# mainSchem.net
KiCad netlist of a schematic drawn in Altium Designer
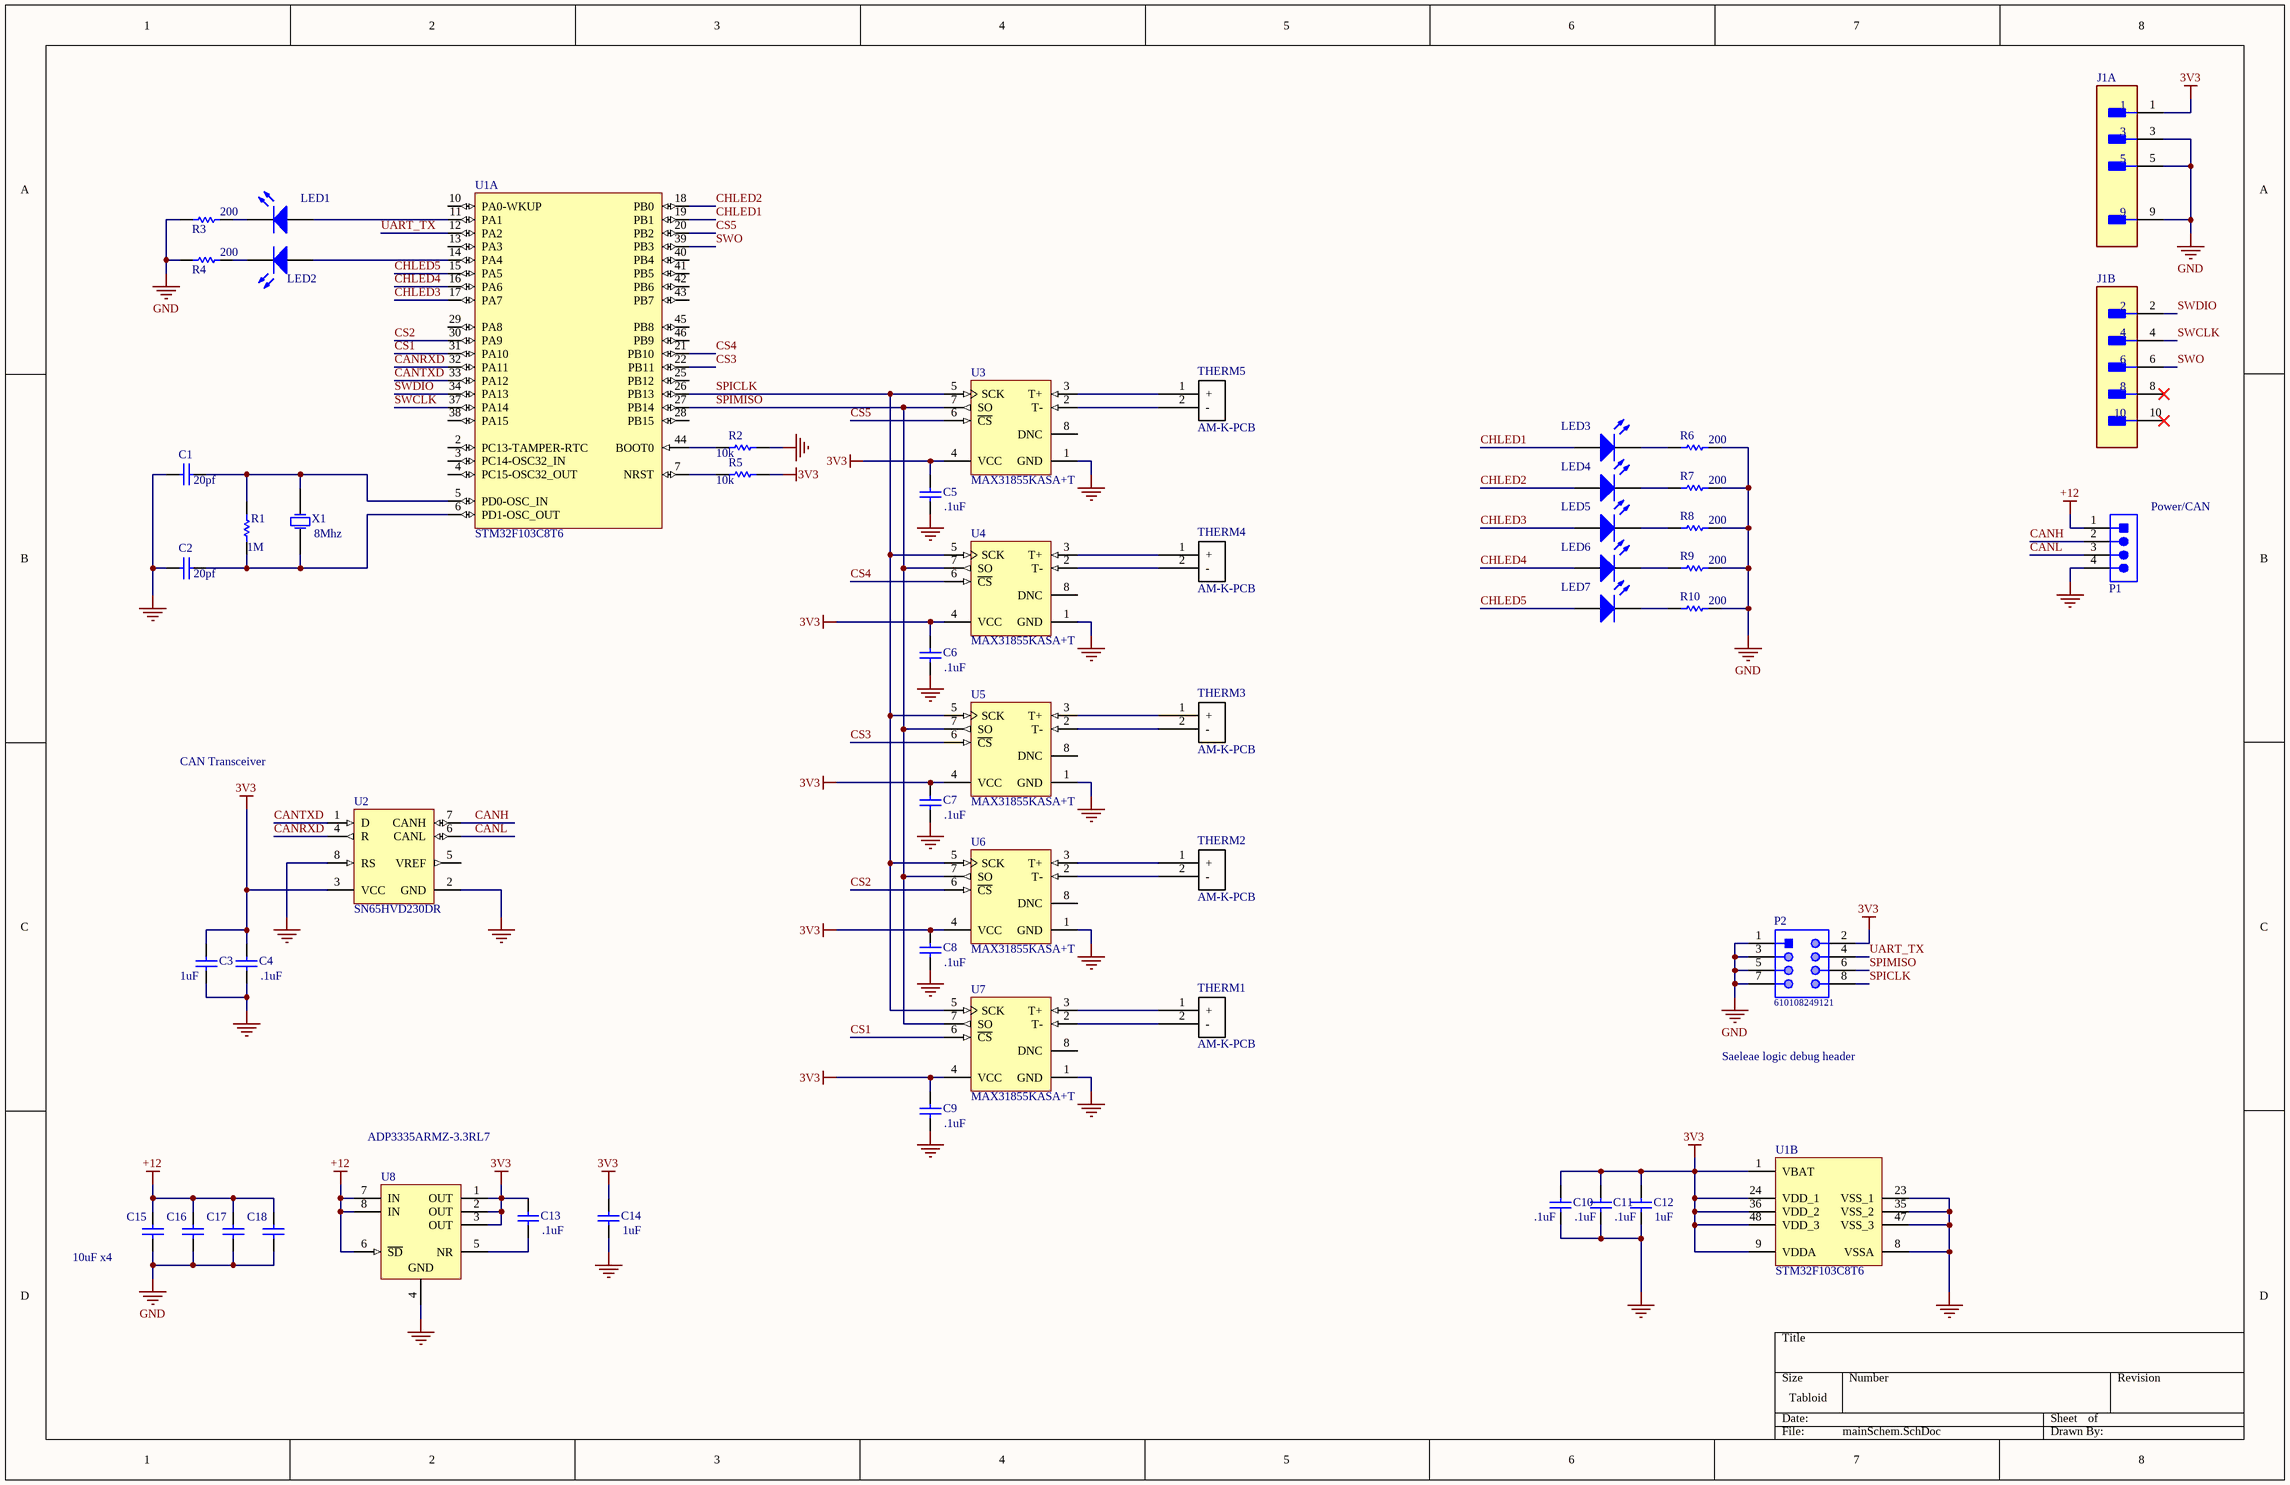
[diagram p0: mainSchem.SchDoc]

(export (version "E")
  (design (tool "Eeschema 10.0.6"))
  (components
    (comp (ref "C1")
      (value "08051A200JAT2A")
      (footprint "CAPC2013X140X50NL20T25")
      (fields (field (name "MANUFACTURER") "AVX Interconnect / Elco"))
      (libsource (lib "Altium Content Vault") (part "CAP"))
    )
    (comp (ref "C2")
      (value "08051A200JAT2A")
      (footprint "CAPC2013X140X50NL20T25")
      (fields (field (name "MANUFACTURER") "AVX Interconnect / Elco"))
      (libsource (lib "Altium Content Vault") (part "CAP"))
    )
    (comp (ref "C3")
      (value "GRM31MR71H105KA88L")
      (footprint "CAPC3216X125X55LL15T25")
      (description "Chip Capacitor, 1 uF, +/- 10%, 50 V, -55 to 125 degC, 1206 (3216 Metric), RoHS, Tape and Reel")
      (fields (field (name "TOLERANCE") "10%") (field (name "MANUFACTURER") "Murata"))
      (libsource (lib "Altium Content Vault") (part "CAP-NP-2"))
    )
    (comp (ref "C4")
      (value "12065C104KAT2A")
      (footprint "CAPC3216X94X50ML20T25")
      (description "Chip Capacitor, Ceramic, 100 nF, 10%, 50 V, 1206, RoHS, Tape and Reel")
      (fields (field (name "MANUFACTURER") "AVX"))
      (libsource (lib "Altium Content Vault") (part "CAP-NP-2"))
    )
    (comp (ref "C5")
      (value "CGA3E2X7R1H104K080AA")
      (footprint "CAPC1608X90X20LL10")
      (description "Chip Capacitor, 0.1 uF, +/- 10%, 50 V, -55 to 125 degC, 0603 (1608 Metric), RoHS, Tape and Reel")
      (fields (field (name "VOLTAGE") "50V") (field (name "TOLERANCE") "10%"))
      (libsource (lib "Altium Content Vault") (part "CAP-NP-2"))
    )
    (comp (ref "C6")
      (value "CGA3E2X7R1H104K080AA")
      (footprint "CAPC1608X90X20LL10")
      (description "Chip Capacitor, 0.1 uF, +/- 10%, 50 V, -55 to 125 degC, 0603 (1608 Metric), RoHS, Tape and Reel")
      (fields (field (name "VOLTAGE") "50V") (field (name "TOLERANCE") "10%"))
      (libsource (lib "Altium Content Vault") (part "CAP-NP-2"))
    )
    (comp (ref "C7")
      (value "CGA3E2X7R1H104K080AA")
      (footprint "CAPC1608X90X20LL10")
      (description "Chip Capacitor, 0.1 uF, +/- 10%, 50 V, -55 to 125 degC, 0603 (1608 Metric), RoHS, Tape and Reel")
      (fields (field (name "VOLTAGE") "50V") (field (name "TOLERANCE") "10%"))
      (libsource (lib "Altium Content Vault") (part "CAP-NP-2"))
    )
    (comp (ref "C8")
      (value "CGA3E2X7R1H104K080AA")
      (footprint "CAPC1608X90X20LL10")
      (description "Chip Capacitor, 0.1 uF, +/- 10%, 50 V, -55 to 125 degC, 0603 (1608 Metric), RoHS, Tape and Reel")
      (fields (field (name "VOLTAGE") "50V") (field (name "TOLERANCE") "10%"))
      (libsource (lib "Altium Content Vault") (part "CAP-NP-2"))
    )
    (comp (ref "C9")
      (value "CGA3E2X7R1H104K080AA")
      (footprint "CAPC1608X90X20LL10")
      (description "Chip Capacitor, 0.1 uF, +/- 10%, 50 V, -55 to 125 degC, 0603 (1608 Metric), RoHS, Tape and Reel")
      (fields (field (name "VOLTAGE") "50V") (field (name "TOLERANCE") "10%"))
      (libsource (lib "Altium Content Vault") (part "CAP-NP-2"))
    )
    (comp (ref "C10")
      (value "12065C104KAT2A")
      (footprint "CAPC3216X94X50ML20T25")
      (description "Chip Capacitor, Ceramic, 100 nF, 10%, 50 V, 1206, RoHS, Tape and Reel")
      (fields (field (name "MANUFACTURER") "AVX"))
      (libsource (lib "Altium Content Vault") (part "CAP-NP-2"))
    )
    (comp (ref "C11")
      (value "12065C104KAT2A")
      (footprint "CAPC3216X94X50ML20T25")
      (description "Chip Capacitor, Ceramic, 100 nF, 10%, 50 V, 1206, RoHS, Tape and Reel")
      (fields (field (name "MANUFACTURER") "AVX"))
      (libsource (lib "Altium Content Vault") (part "CAP-NP-2"))
    )
    (comp (ref "C12")
      (value "12065C104KAT2A")
      (footprint "CAPC3216X94X50ML20T25")
      (description "Chip Capacitor, Ceramic, 100 nF, 10%, 50 V, 1206, RoHS, Tape and Reel")
      (fields (field (name "MANUFACTURER") "AVX"))
      (libsource (lib "Altium Content Vault") (part "CAP-NP-2"))
    )
    (comp (ref "C13")
      (value "CGA3E2X7R1H104K080AA")
      (footprint "CAPC1608X90X20LL10")
      (description "Chip Capacitor, 0.1 uF, +/- 10%, 50 V, -55 to 125 degC, 0603 (1608 Metric), RoHS, Tape and Reel")
      (fields (field (name "VOLTAGE") "50V") (field (name "TOLERANCE") "10%"))
      (libsource (lib "Altium Content Vault") (part "CAP-NP-2"))
    )
    (comp (ref "C14")
      (value "GRM31MR71H105KA88L")
      (footprint "CAPC3216X125X55LL15T25")
      (description "Chip Capacitor, 1 uF, +/- 10%, 50 V, -55 to 125 degC, 1206 (3216 Metric), RoHS, Tape and Reel")
      (fields (field (name "TOLERANCE") "10%") (field (name "MANUFACTURER") "Murata"))
      (libsource (lib "Altium Content Vault") (part "CAP-NP-2"))
    )
    (comp (ref "C15")
      (value "CGA5L3X5R1H106K160AB")
      (footprint "CAPC3216X190X20LL20")
      (description "Chip Capacitor, 10 uF, +/- 10%, 50 V, -55 to 85 degC, 1206 (3216 Metric), RoHS, Tape and Reel")
      (fields (field (name "MANUFACTURER") "TDK") (field (name "TOLERANCE") "10%"))
      (libsource (lib "Altium Content Vault") (part "CAP-NP-2"))
    )
    (comp (ref "C16")
      (value "CGA5L3X5R1H106K160AB")
      (footprint "CAPC3216X190X20LL20")
      (description "Chip Capacitor, 10 uF, +/- 10%, 50 V, -55 to 85 degC, 1206 (3216 Metric), RoHS, Tape and Reel")
      (fields (field (name "MANUFACTURER") "TDK") (field (name "TOLERANCE") "10%"))
      (libsource (lib "Altium Content Vault") (part "CAP-NP-2"))
    )
    (comp (ref "C17")
      (value "CGA5L3X5R1H106K160AB")
      (footprint "CAPC3216X190X20LL20")
      (description "Chip Capacitor, 10 uF, +/- 10%, 50 V, -55 to 85 degC, 1206 (3216 Metric), RoHS, Tape and Reel")
      (fields (field (name "MANUFACTURER") "TDK") (field (name "TOLERANCE") "10%"))
      (libsource (lib "Altium Content Vault") (part "CAP-NP-2"))
    )
    (comp (ref "C18")
      (value "CGA5L3X5R1H106K160AB")
      (footprint "CAPC3216X190X20LL20")
      (description "Chip Capacitor, 10 uF, +/- 10%, 50 V, -55 to 85 degC, 1206 (3216 Metric), RoHS, Tape and Reel")
      (fields (field (name "MANUFACTURER") "TDK") (field (name "TOLERANCE") "10%"))
      (libsource (lib "Altium Content Vault") (part "CAP-NP-2"))
    )
    (comp (ref "J1")
      (value "FTSH-105-01-L-DV-007-K")
      (footprint "FP-FTSH-105-01-L-DV-007-K-MFG")
      (description "CONN HEADER SMD 10POS 1.27MM")
      (fields
        (field (name "OCTOPART") "https://octopart.com/ftsh-105-01-l-dv-007-k-samtec-53647300")
        (field (name "MANUFACTURER") "Samtec")
      )
      (libsource (lib "Altium Content Vault") (part "7c368be3265735b2816d0cab4417f87"))
    )
    (comp (ref "LED1")
      (value "150120GS75000")
      (footprint "1206_A")
      (description "SMD mono-color Chip LED, WL-SMCW, Green")
      (fields (field (name "MANUFACTURER") "Wuerth Elektronik"))
      (libsource (lib "Altium Content Vault") (part "WE-LED_K1A2-2"))
    )
    (comp (ref "LED2")
      (value "150120GS75000")
      (footprint "1206_A")
      (description "SMD mono-color Chip LED, WL-SMCW, Green")
      (fields (field (name "MANUFACTURER") "Wuerth Elektronik"))
      (libsource (lib "Altium Content Vault") (part "WE-LED_K1A2-2"))
    )
    (comp (ref "LED3")
      (value "150120GS75000")
      (footprint "1206_A")
      (description "SMD mono-color Chip LED, WL-SMCW, Green")
      (fields (field (name "MANUFACTURER") "Wuerth Elektronik"))
      (libsource (lib "Altium Content Vault") (part "WE-LED_K1A2-2"))
    )
    (comp (ref "LED4")
      (value "150120GS75000")
      (footprint "1206_A")
      (description "SMD mono-color Chip LED, WL-SMCW, Green")
      (fields (field (name "MANUFACTURER") "Wuerth Elektronik"))
      (libsource (lib "Altium Content Vault") (part "WE-LED_K1A2-2"))
    )
    (comp (ref "LED5")
      (value "150120GS75000")
      (footprint "1206_A")
      (description "SMD mono-color Chip LED, WL-SMCW, Green")
      (fields (field (name "MANUFACTURER") "Wuerth Elektronik"))
      (libsource (lib "Altium Content Vault") (part "WE-LED_K1A2-2"))
    )
    (comp (ref "LED6")
      (value "150120GS75000")
      (footprint "1206_A")
      (description "SMD mono-color Chip LED, WL-SMCW, Green")
      (fields (field (name "MANUFACTURER") "Wuerth Elektronik"))
      (libsource (lib "Altium Content Vault") (part "WE-LED_K1A2-2"))
    )
    (comp (ref "LED7")
      (value "150120GS75000")
      (footprint "1206_A")
      (description "SMD mono-color Chip LED, WL-SMCW, Green")
      (fields (field (name "MANUFACTURER") "Wuerth Elektronik"))
      (libsource (lib "Altium Content Vault") (part "WE-LED_K1A2-2"))
    )
    (comp (ref "P1")
      (value "B4B-PH-K-S(LF)(SN)")
      (footprint "JST-B4B-PH-K-S_V")
      (fields (field (name "MANUFACTURER") "JST"))
      (libsource (lib "Altium Content Vault") (part "CN-1P-M-R4"))
    )
    (comp (ref "P2")
      (value "610108249121")
      (footprint "610108249121")
      (description "SMT Angled Pin Header WR-PHD, Pitch 2.54 mm, Dual Row, 8 pins")
      (fields (field (name "MANUFACTURER") "Wurth Elektronik") (field (name "PUBLISHER") "WurthElektronik"))
      (libsource (lib "Altium Content Vault") (part "WE-CN-2P-M-R8"))
    )
    (comp (ref "R1")
      (value "ERJ-8ENF1004V")
      (footprint "RESC3216X70X50NL05T20")
      (fields (field (name "MANUFACTURER") "Panasonic"))
      (libsource (lib "Altium Content Vault") (part "RES"))
    )
    (comp (ref "R2")
      (value "ERJ3EKF1002V")
      (footprint "RESC1609X55X30LL15T15")
      (description "Chip Resistor, 10 KOhm, +/- 1%, 0.1 W, -55 to 155 degC, 0603 (1608 Metric), RoHS, Tape and Reel")
      (fields (field (name "TOLERANCE") "1%") (field (name "MANUFACTURER") "Panasonic"))
      (libsource (lib "Altium Content Vault") (part "RES-2"))
    )
    (comp (ref "R3")
      (value "CRCW1206200RFKEA")
      (footprint "RESC3216X60X45ML10T20")
      (fields (field (name "MANUFACTURER") "Vishay Dale"))
      (libsource (lib "Altium Content Vault") (part "RES"))
    )
    (comp (ref "R4")
      (value "CRCW1206200RFKEA")
      (footprint "RESC3216X60X45ML10T20")
      (fields (field (name "MANUFACTURER") "Vishay Dale"))
      (libsource (lib "Altium Content Vault") (part "RES"))
    )
    (comp (ref "R5")
      (value "ERJ3EKF1002V")
      (footprint "RESC1609X55X30LL15T15")
      (description "Chip Resistor, 10 KOhm, +/- 1%, 0.1 W, -55 to 155 degC, 0603 (1608 Metric), RoHS, Tape and Reel")
      (fields (field (name "TOLERANCE") "1%") (field (name "MANUFACTURER") "Panasonic"))
      (libsource (lib "Altium Content Vault") (part "RES-2"))
    )
    (comp (ref "R6")
      (value "CRCW0603200RFKEA")
      (footprint "RESC1609X50X30NL10T20")
      (fields (field (name "MANUFACTURER") "Vishay Dale"))
      (libsource (lib "Altium Content Vault") (part "RES"))
    )
    (comp (ref "R7")
      (value "CRCW0603200RFKEA")
      (footprint "RESC1609X50X30NL10T20")
      (fields (field (name "MANUFACTURER") "Vishay Dale"))
      (libsource (lib "Altium Content Vault") (part "RES"))
    )
    (comp (ref "R8")
      (value "CRCW0603200RFKEA")
      (footprint "RESC1609X50X30NL10T20")
      (fields (field (name "MANUFACTURER") "Vishay Dale"))
      (libsource (lib "Altium Content Vault") (part "RES"))
    )
    (comp (ref "R9")
      (value "CRCW0603200RFKEA")
      (footprint "RESC1609X50X30NL10T20")
      (fields (field (name "MANUFACTURER") "Vishay Dale"))
      (libsource (lib "Altium Content Vault") (part "RES"))
    )
    (comp (ref "R10")
      (value "CRCW0603200RFKEA")
      (footprint "RESC1609X50X30NL10T20")
      (fields (field (name "MANUFACTURER") "Vishay Dale"))
      (libsource (lib "Altium Content Vault") (part "RES"))
    )
    (comp (ref "THERM1")
      (value "AM-K-PCB")
      (footprint "Type K Connector")
      (libsource (lib "Type K Connector Lib") (part "Type K Thermocoulple Conn."))
    )
    (comp (ref "THERM2")
      (value "AM-K-PCB")
      (footprint "Type K Connector")
      (libsource (lib "Type K Connector Lib") (part "Type K Thermocoulple Conn."))
    )
    (comp (ref "THERM3")
      (value "AM-K-PCB")
      (footprint "Type K Connector")
      (libsource (lib "Type K Connector Lib") (part "Type K Thermocoulple Conn."))
    )
    (comp (ref "THERM4")
      (value "AM-K-PCB")
      (footprint "Type K Connector")
      (libsource (lib "Type K Connector Lib") (part "Type K Thermocoulple Conn."))
    )
    (comp (ref "THERM5")
      (value "AM-K-PCB")
      (footprint "Type K Connector")
      (libsource (lib "Type K Connector Lib") (part "Type K Thermocoulple Conn."))
    )
    (comp (ref "U1")
      (value "STM32F103C8T6")
      (footprint "STM-LQFP48_L")
      (libsource (lib "Altium Content Vault") (part "MC-ARM-STM32F103X8_B-SQ48"))
    )
    (comp (ref "U2")
      (value "SN65HVD230DR")
      (footprint "D0008A_L")
      (fields (field (name "MANUFACTURER") "Texas Instruments"))
      (libsource (lib "Altium Content Vault") (part "TI-SN65HVD230-SOIC_D-8"))
    )
    (comp (ref "U3")
      (value "MAX31855KASA+T")
      (footprint "MAXM-S8+4_N")
      (fields (field (name "GENERIC PART NUMBER") "MAX31855"))
      (libsource (lib "Altium Content Vault") (part "MAX31855-S8+4"))
    )
    (comp (ref "U4")
      (value "MAX31855KASA+T")
      (footprint "MAXM-S8+4_N")
      (fields (field (name "GENERIC PART NUMBER") "MAX31855"))
      (libsource (lib "Altium Content Vault") (part "MAX31855-S8+4"))
    )
    (comp (ref "U5")
      (value "MAX31855KASA+T")
      (footprint "MAXM-S8+4_N")
      (fields (field (name "GENERIC PART NUMBER") "MAX31855"))
      (libsource (lib "Altium Content Vault") (part "MAX31855-S8+4"))
    )
    (comp (ref "U6")
      (value "MAX31855KASA+T")
      (footprint "MAXM-S8+4_N")
      (fields (field (name "GENERIC PART NUMBER") "MAX31855"))
      (libsource (lib "Altium Content Vault") (part "MAX31855-S8+4"))
    )
    (comp (ref "U7")
      (value "MAX31855KASA+T")
      (footprint "MAXM-S8+4_N")
      (fields (field (name "GENERIC PART NUMBER") "MAX31855"))
      (libsource (lib "Altium Content Vault") (part "MAX31855-S8+4"))
    )
    (comp (ref "U8")
      (value "ADP3335ARMZ-3.3RL7")
      (footprint "ADI-RM-8_L")
      (fields (field (name "MANUFACTURER") "Analog Devices"))
      (libsource (lib "Altium Content Vault") (part "ADI-ADP3335-RM-8"))
    )
    (comp (ref "X1")
      (value "ABM3-8.000MHZ-D2Y-T")
      (footprint "ABRA-ABM3-2_V")
      (description "Miniature Ceramic Crystal, 8 MHz, -40 to 85 degC, 2-Pin SMD, RoHS, Tape and Reel")
      (fields (field (name "MANUFACTURER") "ABRACON") (field (name "TOLERANCE") "20PPM"))
      (libsource (lib "Altium Content Vault") (part "XTAL_1-2-2"))
    )
  )
  (nets
    (net (code "1") (name "+12") (class "Default")
      (node (ref "C15") (pin "1") (pinfunction "1_1") (pintype "passive"))
      (node (ref "C16") (pin "1") (pinfunction "1_1") (pintype "passive"))
      (node (ref "C17") (pin "1") (pinfunction "1_1") (pintype "passive"))
      (node (ref "C18") (pin "1") (pinfunction "1_1") (pintype "passive"))
      (node (ref "P1") (pin "1") (pinfunction "1_1") (pintype "passive"))
      (node (ref "U8") (pin "6") (pinfunction "~{SD}_6") (pintype "input"))
      (node (ref "U8") (pin "7") (pinfunction "IN_7") (pintype "power_in"))
      (node (ref "U8") (pin "8") (pinfunction "IN_8") (pintype "power_in"))
    )
    (net (code "2") (name "/CANH") (class "Default")
      (node (ref "P1") (pin "2") (pinfunction "2_2") (pintype "passive"))
      (node (ref "U2") (pin "7") (pinfunction "CANH_7") (pintype "bidirectional"))
    )
    (net (code "3") (name "/CANL") (class "Default")
      (node (ref "P1") (pin "3") (pinfunction "3_3") (pintype "passive"))
      (node (ref "U2") (pin "6") (pinfunction "CANL_6") (pintype "bidirectional"))
    )
    (net (code "4") (name "/CANRXD") (class "Default")
      (node (ref "U1") (pin "32") (pinfunction "PA11_32") (pintype "bidirectional"))
      (node (ref "U2") (pin "4") (pinfunction "R_4") (pintype "output"))
    )
    (net (code "5") (name "/CANTXD") (class "Default")
      (node (ref "U1") (pin "33") (pinfunction "PA12_33") (pintype "bidirectional"))
      (node (ref "U2") (pin "1") (pinfunction "D_1") (pintype "input"))
    )
    (net (code "6") (name "/CHLED1") (class "Default")
      (node (ref "LED3") (pin "2") (pinfunction "A_2") (pintype "passive"))
      (node (ref "U1") (pin "19") (pinfunction "PB1_19") (pintype "bidirectional"))
    )
    (net (code "7") (name "/CHLED2") (class "Default")
      (node (ref "LED4") (pin "2") (pinfunction "A_2") (pintype "passive"))
      (node (ref "U1") (pin "18") (pinfunction "PB0_18") (pintype "bidirectional"))
    )
    (net (code "8") (name "/CHLED3") (class "Default")
      (node (ref "LED5") (pin "2") (pinfunction "A_2") (pintype "passive"))
      (node (ref "U1") (pin "17") (pinfunction "PA7_17") (pintype "bidirectional"))
    )
    (net (code "9") (name "/CHLED4") (class "Default")
      (node (ref "LED6") (pin "2") (pinfunction "A_2") (pintype "passive"))
      (node (ref "U1") (pin "16") (pinfunction "PA6_16") (pintype "bidirectional"))
    )
    (net (code "10") (name "/CHLED5") (class "Default")
      (node (ref "LED7") (pin "2") (pinfunction "A_2") (pintype "passive"))
      (node (ref "U1") (pin "15") (pinfunction "PA5_15") (pintype "bidirectional"))
    )
    (net (code "11") (name "/CS1") (class "Default")
      (node (ref "U1") (pin "31") (pinfunction "PA10_31") (pintype "bidirectional"))
      (node (ref "U7") (pin "6") (pinfunction "~{CS}_6") (pintype "input"))
    )
    (net (code "12") (name "/CS2") (class "Default")
      (node (ref "U1") (pin "30") (pinfunction "PA9_30") (pintype "bidirectional"))
      (node (ref "U6") (pin "6") (pinfunction "~{CS}_6") (pintype "input"))
    )
    (net (code "13") (name "/CS3") (class "Default")
      (node (ref "U1") (pin "22") (pinfunction "PB11_22") (pintype "bidirectional"))
      (node (ref "U5") (pin "6") (pinfunction "~{CS}_6") (pintype "input"))
    )
    (net (code "14") (name "/CS4") (class "Default")
      (node (ref "U1") (pin "21") (pinfunction "PB10_21") (pintype "bidirectional"))
      (node (ref "U4") (pin "6") (pinfunction "~{CS}_6") (pintype "input"))
    )
    (net (code "15") (name "/CS5") (class "Default")
      (node (ref "U1") (pin "20") (pinfunction "PB2_20") (pintype "bidirectional"))
      (node (ref "U3") (pin "6") (pinfunction "~{CS}_6") (pintype "input"))
    )
    (net (code "16") (name "/SPICLK") (class "Default")
      (node (ref "P2") (pin "8") (pinfunction "8_8") (pintype "passive"))
      (node (ref "U1") (pin "26") (pinfunction "PB13_26") (pintype "bidirectional"))
      (node (ref "U3") (pin "5") (pinfunction "SCK_5") (pintype "input"))
      (node (ref "U4") (pin "5") (pinfunction "SCK_5") (pintype "input"))
      (node (ref "U5") (pin "5") (pinfunction "SCK_5") (pintype "input"))
      (node (ref "U6") (pin "5") (pinfunction "SCK_5") (pintype "input"))
      (node (ref "U7") (pin "5") (pinfunction "SCK_5") (pintype "input"))
    )
    (net (code "17") (name "/SPIMISO") (class "Default")
      (node (ref "P2") (pin "6") (pinfunction "6_6") (pintype "passive"))
      (node (ref "U1") (pin "27") (pinfunction "PB14_27") (pintype "bidirectional"))
      (node (ref "U3") (pin "7") (pinfunction "SO_7") (pintype "output"))
      (node (ref "U4") (pin "7") (pinfunction "SO_7") (pintype "output"))
      (node (ref "U5") (pin "7") (pinfunction "SO_7") (pintype "output"))
      (node (ref "U6") (pin "7") (pinfunction "SO_7") (pintype "output"))
      (node (ref "U7") (pin "7") (pinfunction "SO_7") (pintype "output"))
    )
    (net (code "18") (name "/SWCLK") (class "Default")
      (node (ref "J1") (pin "4") (pinfunction "4_4") (pintype "passive"))
      (node (ref "U1") (pin "37") (pinfunction "PA14_37") (pintype "bidirectional"))
    )
    (net (code "19") (name "/SWDIO") (class "Default")
      (node (ref "J1") (pin "2") (pinfunction "2_2") (pintype "passive"))
      (node (ref "U1") (pin "34") (pinfunction "PA13_34") (pintype "bidirectional"))
    )
    (net (code "20") (name "/SWO") (class "Default")
      (node (ref "J1") (pin "6") (pinfunction "6_6") (pintype "passive"))
      (node (ref "U1") (pin "39") (pinfunction "PB3_39") (pintype "bidirectional"))
    )
    (net (code "21") (name "/UART_TX") (class "Default")
      (node (ref "P2") (pin "4") (pinfunction "4_4") (pintype "passive"))
      (node (ref "U1") (pin "12") (pinfunction "PA2_12") (pintype "bidirectional"))
    )
    (net (code "22") (name "3V3") (class "Default")
      (node (ref "C10") (pin "1") (pinfunction "1_1") (pintype "passive"))
      (node (ref "C11") (pin "1") (pinfunction "1_1") (pintype "passive"))
      (node (ref "C12") (pin "1") (pinfunction "1_1") (pintype "passive"))
      (node (ref "C13") (pin "1") (pinfunction "1_1") (pintype "passive"))
      (node (ref "C14") (pin "1") (pinfunction "1_1") (pintype "passive"))
      (node (ref "C3") (pin "1") (pinfunction "1_1") (pintype "passive"))
      (node (ref "C4") (pin "1") (pinfunction "1_1") (pintype "passive"))
      (node (ref "C5") (pin "1") (pinfunction "1_1") (pintype "passive"))
      (node (ref "C6") (pin "1") (pinfunction "1_1") (pintype "passive"))
      (node (ref "C7") (pin "1") (pinfunction "1_1") (pintype "passive"))
      (node (ref "C8") (pin "1") (pinfunction "1_1") (pintype "passive"))
      (node (ref "C9") (pin "1") (pinfunction "1_1") (pintype "passive"))
      (node (ref "J1") (pin "1") (pinfunction "1_1") (pintype "passive"))
      (node (ref "P2") (pin "2") (pinfunction "2_2") (pintype "passive"))
      (node (ref "R5") (pin "2") (pinfunction "2_2") (pintype "passive"))
      (node (ref "U1") (pin "1") (pinfunction "VBAT_1") (pintype "power_in"))
      (node (ref "U1") (pin "24") (pinfunction "VDD_1_24") (pintype "power_in"))
      (node (ref "U1") (pin "36") (pinfunction "VDD_2_36") (pintype "power_in"))
      (node (ref "U1") (pin "48") (pinfunction "VDD_3_48") (pintype "power_in"))
      (node (ref "U1") (pin "9") (pinfunction "VDDA_9") (pintype "power_in"))
      (node (ref "U2") (pin "3") (pinfunction "VCC_3") (pintype "power_in"))
      (node (ref "U3") (pin "4") (pinfunction "VCC_4") (pintype "power_in"))
      (node (ref "U4") (pin "4") (pinfunction "VCC_4") (pintype "power_in"))
      (node (ref "U5") (pin "4") (pinfunction "VCC_4") (pintype "power_in"))
      (node (ref "U6") (pin "4") (pinfunction "VCC_4") (pintype "power_in"))
      (node (ref "U7") (pin "4") (pinfunction "VCC_4") (pintype "power_in"))
      (node (ref "U8") (pin "1") (pinfunction "OUT_1") (pintype "power_in"))
      (node (ref "U8") (pin "2") (pinfunction "OUT_2") (pintype "power_in"))
      (node (ref "U8") (pin "3") (pinfunction "OUT_3") (pintype "power_in"))
    )
    (net (code "23") (name "GND") (class "Default")
      (node (ref "C1") (pin "1") (pinfunction "1_1") (pintype "passive"))
      (node (ref "C10") (pin "2") (pinfunction "2_2") (pintype "passive"))
      (node (ref "C11") (pin "2") (pinfunction "2_2") (pintype "passive"))
      (node (ref "C12") (pin "2") (pinfunction "2_2") (pintype "passive"))
      (node (ref "C14") (pin "2") (pinfunction "2_2") (pintype "passive"))
      (node (ref "C15") (pin "2") (pinfunction "2_2") (pintype "passive"))
      (node (ref "C16") (pin "2") (pinfunction "2_2") (pintype "passive"))
      (node (ref "C17") (pin "2") (pinfunction "2_2") (pintype "passive"))
      (node (ref "C18") (pin "2") (pinfunction "2_2") (pintype "passive"))
      (node (ref "C2") (pin "1") (pinfunction "1_1") (pintype "passive"))
      (node (ref "C3") (pin "2") (pinfunction "2_2") (pintype "passive"))
      (node (ref "C4") (pin "2") (pinfunction "2_2") (pintype "passive"))
      (node (ref "C5") (pin "2") (pinfunction "2_2") (pintype "passive"))
      (node (ref "C6") (pin "2") (pinfunction "2_2") (pintype "passive"))
      (node (ref "C7") (pin "2") (pinfunction "2_2") (pintype "passive"))
      (node (ref "C8") (pin "2") (pinfunction "2_2") (pintype "passive"))
      (node (ref "C9") (pin "2") (pinfunction "2_2") (pintype "passive"))
      (node (ref "J1") (pin "3") (pinfunction "3_3") (pintype "passive"))
      (node (ref "J1") (pin "5") (pinfunction "5_5") (pintype "passive"))
      (node (ref "J1") (pin "9") (pinfunction "9_9") (pintype "passive"))
      (node (ref "P1") (pin "4") (pinfunction "4_4") (pintype "passive"))
      (node (ref "P2") (pin "1") (pinfunction "1_1") (pintype "passive"))
      (node (ref "P2") (pin "3") (pinfunction "3_3") (pintype "passive"))
      (node (ref "P2") (pin "5") (pinfunction "5_5") (pintype "passive"))
      (node (ref "P2") (pin "7") (pinfunction "7_7") (pintype "passive"))
      (node (ref "R10") (pin "2") (pinfunction "2_2") (pintype "passive"))
      (node (ref "R2") (pin "2") (pinfunction "2_2") (pintype "passive"))
      (node (ref "R3") (pin "1") (pinfunction "1_1") (pintype "passive"))
      (node (ref "R4") (pin "1") (pinfunction "1_1") (pintype "passive"))
      (node (ref "R6") (pin "2") (pinfunction "2_2") (pintype "passive"))
      (node (ref "R7") (pin "2") (pinfunction "2_2") (pintype "passive"))
      (node (ref "R8") (pin "2") (pinfunction "2_2") (pintype "passive"))
      (node (ref "R9") (pin "2") (pinfunction "2_2") (pintype "passive"))
      (node (ref "U1") (pin "23") (pinfunction "VSS_1_23") (pintype "power_in"))
      (node (ref "U1") (pin "35") (pinfunction "VSS_2_35") (pintype "power_in"))
      (node (ref "U1") (pin "47") (pinfunction "VSS_3_47") (pintype "power_in"))
      (node (ref "U1") (pin "8") (pinfunction "VSSA_8") (pintype "power_in"))
      (node (ref "U2") (pin "2") (pinfunction "GND_2") (pintype "power_in"))
      (node (ref "U2") (pin "8") (pinfunction "RS_8") (pintype "input"))
      (node (ref "U3") (pin "1") (pinfunction "GND_1") (pintype "power_in"))
      (node (ref "U4") (pin "1") (pinfunction "GND_1") (pintype "power_in"))
      (node (ref "U5") (pin "1") (pinfunction "GND_1") (pintype "power_in"))
      (node (ref "U6") (pin "1") (pinfunction "GND_1") (pintype "power_in"))
      (node (ref "U7") (pin "1") (pinfunction "GND_1") (pintype "power_in"))
      (node (ref "U8") (pin "4") (pinfunction "GND_4") (pintype "power_in"))
    )
    (net (code "24") (name "Net-(LED1-A)") (class "Default")
      (node (ref "LED1") (pin "2") (pinfunction "A_2") (pintype "passive"))
      (node (ref "U1") (pin "11") (pinfunction "PA1_11") (pintype "bidirectional"))
    )
    (net (code "25") (name "Net-(LED1-K)") (class "Default")
      (node (ref "LED1") (pin "1") (pinfunction "K_1") (pintype "passive"))
      (node (ref "R3") (pin "2") (pinfunction "2_2") (pintype "passive"))
    )
    (net (code "26") (name "Net-(LED2-A)") (class "Default")
      (node (ref "LED2") (pin "2") (pinfunction "A_2") (pintype "passive"))
      (node (ref "U1") (pin "14") (pinfunction "PA4_14") (pintype "bidirectional"))
    )
    (net (code "27") (name "Net-(LED2-K)") (class "Default")
      (node (ref "LED2") (pin "1") (pinfunction "K_1") (pintype "passive"))
      (node (ref "R4") (pin "2") (pinfunction "2_2") (pintype "passive"))
    )
    (net (code "28") (name "Net-(LED3-K)") (class "Default")
      (node (ref "LED3") (pin "1") (pinfunction "K_1") (pintype "passive"))
      (node (ref "R6") (pin "1") (pinfunction "1_1") (pintype "passive"))
    )
    (net (code "29") (name "Net-(LED4-K)") (class "Default")
      (node (ref "LED4") (pin "1") (pinfunction "K_1") (pintype "passive"))
      (node (ref "R7") (pin "1") (pinfunction "1_1") (pintype "passive"))
    )
    (net (code "30") (name "Net-(LED5-K)") (class "Default")
      (node (ref "LED5") (pin "1") (pinfunction "K_1") (pintype "passive"))
      (node (ref "R8") (pin "1") (pinfunction "1_1") (pintype "passive"))
    )
    (net (code "31") (name "Net-(LED6-K)") (class "Default")
      (node (ref "LED6") (pin "1") (pinfunction "K_1") (pintype "passive"))
      (node (ref "R9") (pin "1") (pinfunction "1_1") (pintype "passive"))
    )
    (net (code "32") (name "Net-(LED7-K)") (class "Default")
      (node (ref "LED7") (pin "1") (pinfunction "K_1") (pintype "passive"))
      (node (ref "R10") (pin "1") (pinfunction "1_1") (pintype "passive"))
    )
    (net (code "33") (name "Net-(THERM1-+)") (class "Default")
      (node (ref "THERM1") (pin "1") (pinfunction "+_1") (pintype "passive"))
      (node (ref "U7") (pin "3") (pinfunction "T+_3") (pintype "input"))
    )
    (net (code "34") (name "Net-(THERM1--)") (class "Default")
      (node (ref "THERM1") (pin "2") (pinfunction "-_2") (pintype "passive"))
      (node (ref "U7") (pin "2") (pinfunction "T-_2") (pintype "input"))
    )
    (net (code "35") (name "Net-(THERM2-+)") (class "Default")
      (node (ref "THERM2") (pin "1") (pinfunction "+_1") (pintype "passive"))
      (node (ref "U6") (pin "3") (pinfunction "T+_3") (pintype "input"))
    )
    (net (code "36") (name "Net-(THERM2--)") (class "Default")
      (node (ref "THERM2") (pin "2") (pinfunction "-_2") (pintype "passive"))
      (node (ref "U6") (pin "2") (pinfunction "T-_2") (pintype "input"))
    )
    (net (code "37") (name "Net-(THERM3-+)") (class "Default")
      (node (ref "THERM3") (pin "1") (pinfunction "+_1") (pintype "passive"))
      (node (ref "U5") (pin "3") (pinfunction "T+_3") (pintype "input"))
    )
    (net (code "38") (name "Net-(THERM3--)") (class "Default")
      (node (ref "THERM3") (pin "2") (pinfunction "-_2") (pintype "passive"))
      (node (ref "U5") (pin "2") (pinfunction "T-_2") (pintype "input"))
    )
    (net (code "39") (name "Net-(THERM4-+)") (class "Default")
      (node (ref "THERM4") (pin "1") (pinfunction "+_1") (pintype "passive"))
      (node (ref "U4") (pin "3") (pinfunction "T+_3") (pintype "input"))
    )
    (net (code "40") (name "Net-(THERM4--)") (class "Default")
      (node (ref "THERM4") (pin "2") (pinfunction "-_2") (pintype "passive"))
      (node (ref "U4") (pin "2") (pinfunction "T-_2") (pintype "input"))
    )
    (net (code "41") (name "Net-(THERM5-+)") (class "Default")
      (node (ref "THERM5") (pin "1") (pinfunction "+_1") (pintype "passive"))
      (node (ref "U3") (pin "3") (pinfunction "T+_3") (pintype "input"))
    )
    (net (code "42") (name "Net-(THERM5--)") (class "Default")
      (node (ref "THERM5") (pin "2") (pinfunction "-_2") (pintype "passive"))
      (node (ref "U3") (pin "2") (pinfunction "T-_2") (pintype "input"))
    )
    (net (code "43") (name "Net-(U1A-BOOT0)") (class "Default")
      (node (ref "R2") (pin "1") (pinfunction "1_1") (pintype "passive"))
      (node (ref "U1") (pin "44") (pinfunction "BOOT0_44") (pintype "input"))
    )
    (net (code "44") (name "Net-(U1A-NRST)") (class "Default")
      (node (ref "R5") (pin "1") (pinfunction "1_1") (pintype "passive"))
      (node (ref "U1") (pin "7") (pinfunction "NRST_7") (pintype "bidirectional"))
    )
    (net (code "45") (name "Net-(U1A-PD0-OSC_IN)") (class "Default")
      (node (ref "C1") (pin "2") (pinfunction "2_2") (pintype "passive"))
      (node (ref "R1") (pin "1") (pinfunction "1_1") (pintype "passive"))
      (node (ref "U1") (pin "5") (pinfunction "PD0-OSC_IN_5") (pintype "bidirectional"))
      (node (ref "X1") (pin "1") (pinfunction "X1_1") (pintype "passive"))
    )
    (net (code "46") (name "Net-(U1A-PD1-OSC_OUT)") (class "Default")
      (node (ref "C2") (pin "2") (pinfunction "2_2") (pintype "passive"))
      (node (ref "R1") (pin "2") (pinfunction "2_2") (pintype "passive"))
      (node (ref "U1") (pin "6") (pinfunction "PD1-OSC_OUT_6") (pintype "bidirectional"))
      (node (ref "X1") (pin "2") (pinfunction "X2_2") (pintype "passive"))
    )
    (net (code "47") (name "Net-(U8-NR)") (class "Default")
      (node (ref "C13") (pin "2") (pinfunction "2_2") (pintype "passive"))
      (node (ref "U8") (pin "5") (pinfunction "NR_5") (pintype "passive"))
    )
    (net (code "48") (name "unconnected-(J1-Pad8)") (class "Default")
      (node (ref "J1") (pin "8") (pinfunction "8_8") (pintype "passive+no_connect"))
    )
    (net (code "49") (name "unconnected-(J1-Pad10)") (class "Default")
      (node (ref "J1") (pin "10") (pinfunction "10_10") (pintype "passive+no_connect"))
    )
    (net (code "50") (name "unconnected-(U1A-PA0-WKUP-Pad10)") (class "Default")
      (node (ref "U1") (pin "10") (pinfunction "PA0-WKUP_10") (pintype "bidirectional"))
    )
    (net (code "51") (name "unconnected-(U1A-PA3-Pad13)") (class "Default")
      (node (ref "U1") (pin "13") (pinfunction "PA3_13") (pintype "bidirectional"))
    )
    (net (code "52") (name "unconnected-(U1A-PA8-Pad29)") (class "Default")
      (node (ref "U1") (pin "29") (pinfunction "PA8_29") (pintype "bidirectional"))
    )
    (net (code "53") (name "unconnected-(U1A-PA15-Pad38)") (class "Default")
      (node (ref "U1") (pin "38") (pinfunction "PA15_38") (pintype "bidirectional"))
    )
    (net (code "54") (name "unconnected-(U1A-PB4-Pad40)") (class "Default")
      (node (ref "U1") (pin "40") (pinfunction "PB4_40") (pintype "bidirectional"))
    )
    (net (code "55") (name "unconnected-(U1A-PB5-Pad41)") (class "Default")
      (node (ref "U1") (pin "41") (pinfunction "PB5_41") (pintype "bidirectional"))
    )
    (net (code "56") (name "unconnected-(U1A-PB6-Pad42)") (class "Default")
      (node (ref "U1") (pin "42") (pinfunction "PB6_42") (pintype "bidirectional"))
    )
    (net (code "57") (name "unconnected-(U1A-PB7-Pad43)") (class "Default")
      (node (ref "U1") (pin "43") (pinfunction "PB7_43") (pintype "bidirectional"))
    )
    (net (code "58") (name "unconnected-(U1A-PB8-Pad45)") (class "Default")
      (node (ref "U1") (pin "45") (pinfunction "PB8_45") (pintype "bidirectional"))
    )
    (net (code "59") (name "unconnected-(U1A-PB9-Pad46)") (class "Default")
      (node (ref "U1") (pin "46") (pinfunction "PB9_46") (pintype "bidirectional"))
    )
    (net (code "60") (name "unconnected-(U1A-PB12-Pad25)") (class "Default")
      (node (ref "U1") (pin "25") (pinfunction "PB12_25") (pintype "bidirectional"))
    )
    (net (code "61") (name "unconnected-(U1A-PB15-Pad28)") (class "Default")
      (node (ref "U1") (pin "28") (pinfunction "PB15_28") (pintype "bidirectional"))
    )
    (net (code "62") (name "unconnected-(U1A-PC13-TAMPER-RTC-Pad2)") (class "Default")
      (node (ref "U1") (pin "2") (pinfunction "PC13-TAMPER-RTC_2") (pintype "bidirectional"))
    )
    (net (code "63") (name "unconnected-(U1A-PC14-OSC32_IN-Pad3)") (class "Default")
      (node (ref "U1") (pin "3") (pinfunction "PC14-OSC32_IN_3") (pintype "bidirectional"))
    )
    (net (code "64") (name "unconnected-(U1A-PC15-OSC32_OUT-Pad4)") (class "Default")
      (node (ref "U1") (pin "4") (pinfunction "PC15-OSC32_OUT_4") (pintype "bidirectional"))
    )
    (net (code "65") (name "unconnected-(U2-VREF-Pad5)") (class "Default")
      (node (ref "U2") (pin "5") (pinfunction "VREF_5") (pintype "output"))
    )
    (net (code "66") (name "unconnected-(U3-DNC-Pad8)") (class "Default")
      (node (ref "U3") (pin "8") (pinfunction "DNC_8") (pintype "passive"))
    )
    (net (code "67") (name "unconnected-(U4-DNC-Pad8)") (class "Default")
      (node (ref "U4") (pin "8") (pinfunction "DNC_8") (pintype "passive"))
    )
    (net (code "68") (name "unconnected-(U5-DNC-Pad8)") (class "Default")
      (node (ref "U5") (pin "8") (pinfunction "DNC_8") (pintype "passive"))
    )
    (net (code "69") (name "unconnected-(U6-DNC-Pad8)") (class "Default")
      (node (ref "U6") (pin "8") (pinfunction "DNC_8") (pintype "passive"))
    )
    (net (code "70") (name "unconnected-(U7-DNC-Pad8)") (class "Default")
      (node (ref "U7") (pin "8") (pinfunction "DNC_8") (pintype "passive"))
    )
  )
)
